# 2025_07_18_ftdi.net
KiCad netlist of a schematic drawn in EasyEDA Pro
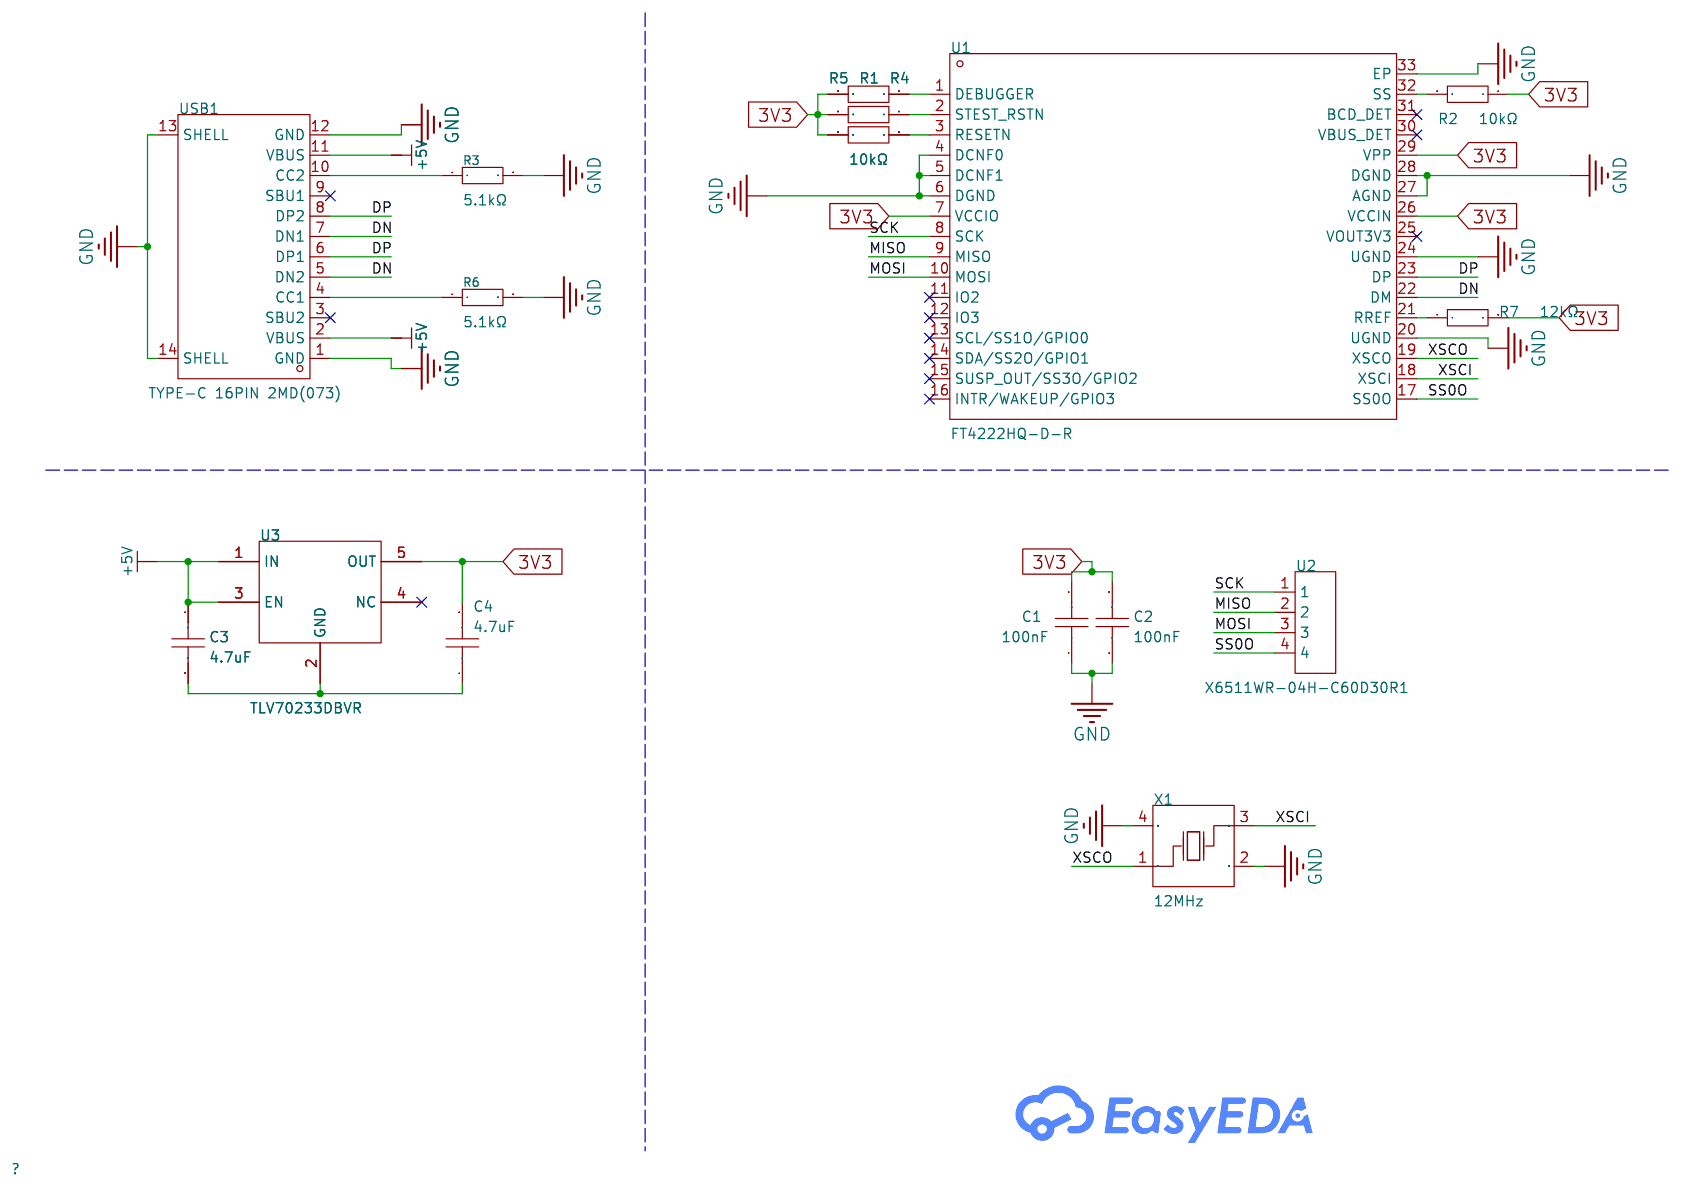
[diagram p0: schematic sheet]

(export (version "E")
  (design (tool "Eeschema 10.0.6"))
  (components
    (comp (ref "C1")
      (value "100nF")
      (footprint "easyedapro:C0402")
      (fields
        (field (name "Manufacturer Part") "CL05B104KO5NNNC")
        (field (name "Manufacturer") "SAMSUNG(三星)")
      )
      (libsource (lib "easyedapro") (part "CL05B104KO5NNNC"))
    )
    (comp (ref "C2")
      (value "100nF")
      (footprint "easyedapro:C0402")
      (fields
        (field (name "Manufacturer Part") "CL05B104KO5NNNC")
        (field (name "Manufacturer") "SAMSUNG(三星)")
      )
      (libsource (lib "easyedapro") (part "CL05B104KO5NNNC"))
    )
    (comp (ref "C3")
      (value "4.7uF")
      (footprint "easyedapro:C0402")
      (fields
        (field (name "Manufacturer Part") "CL05A475MQ5NRNC")
        (field (name "Manufacturer") "SAMSUNG(三星)")
      )
      (libsource (lib "easyedapro") (part "CL05A475MQ5NRNC_C307423"))
    )
    (comp (ref "C4")
      (value "4.7uF")
      (footprint "easyedapro:C0402")
      (fields
        (field (name "Manufacturer Part") "CL05A475MQ5NRNC")
        (field (name "Manufacturer") "SAMSUNG(三星)")
      )
      (libsource (lib "easyedapro") (part "CL05A475MQ5NRNC_C307423"))
    )
    (comp (ref "R1")
      (value "10kΩ")
      (footprint "easyedapro:R0603")
      (fields (field (name "Manufacturer Part") "RC0603FR-0710KL") (field (name "Manufacturer") "YAGEO(国巨)"))
      (libsource (lib "easyedapro") (part "RC0603FR-0710KL"))
    )
    (comp (ref "R2")
      (value "10kΩ")
      (footprint "easyedapro:R0603")
      (fields (field (name "Manufacturer Part") "RC0603FR-0710KL") (field (name "Manufacturer") "YAGEO(国巨)"))
      (libsource (lib "easyedapro") (part "RC0603FR-0710KL"))
    )
    (comp (ref "R3")
      (value "5.1kΩ")
      (footprint "easyedapro:R0402")
      (fields
        (field (name "Manufacturer Part") "0402WGF5101TCE")
        (field (name "Manufacturer") "UNI-ROYAL(厚声)")
      )
      (libsource (lib "easyedapro") (part "0402WGF5101TCE"))
    )
    (comp (ref "R4")
      (value "10kΩ")
      (footprint "easyedapro:R0603")
      (fields (field (name "Manufacturer Part") "RC0603FR-0710KL") (field (name "Manufacturer") "YAGEO(国巨)"))
      (libsource (lib "easyedapro") (part "RC0603FR-0710KL"))
    )
    (comp (ref "R5")
      (value "10kΩ")
      (footprint "easyedapro:R0603")
      (fields (field (name "Manufacturer Part") "RC0603FR-0710KL") (field (name "Manufacturer") "YAGEO(国巨)"))
      (libsource (lib "easyedapro") (part "RC0603FR-0710KL"))
    )
    (comp (ref "R6")
      (value "5.1kΩ")
      (footprint "easyedapro:R0402")
      (fields
        (field (name "Manufacturer Part") "0402WGF5101TCE")
        (field (name "Manufacturer") "UNI-ROYAL(厚声)")
      )
      (libsource (lib "easyedapro") (part "0402WGF5101TCE"))
    )
    (comp (ref "R7")
      (value "12kΩ")
      (footprint "easyedapro:R0402")
      (fields
        (field (name "Manufacturer Part") "0402WGF1202TCE")
        (field (name "Manufacturer") "UNI-ROYAL(厚声)")
      )
      (libsource (lib "easyedapro") (part "0402WGF1202TCE"))
    )
    (comp (ref "U1")
      (value "FT4222HQ-D-R")
      (footprint "easyedapro:QFN-32_L5.0-W5.0-P0.50-BL-EP3.7")
      (fields (field (name "Manufacturer") "FTDI(飞特帝亚)"))
      (libsource (lib "easyedapro") (part "FT4222HQ-D-R"))
    )
    (comp (ref "U2")
      (value "X6511WR-04H-C60D30R1")
      (footprint "easyedapro:HDR-TH_4P-P2.54-H-M-W7.7-P")
      (fields (field (name "Manufacturer") "XKB Connection(中国星坤)"))
      (libsource (lib "easyedapro") (part "X6511WR-04H-C30D60R1"))
    )
    (comp (ref "U3")
      (value "TLV70233DBVR")
      (footprint "easyedapro:SOT-23-5_L3.0-W1.7-P0.95-LS2.8-BR")
      (fields (field (name "Manufacturer") "TI(德州仪器)"))
      (libsource (lib "easyedapro") (part "TLV70233DBVR"))
    )
    (comp (ref "USB1")
      (value "TYPE-C 16PIN 2MD(073)")
      (footprint "easyedapro:USB-C-SMD_TYPE-C-6PIN-2MD-073")
      (fields (field (name "Manufacturer") "SHOU HAN(首韩)"))
      (libsource (lib "easyedapro") (part "TYPE-C 16PIN 2MD(073)"))
    )
    (comp (ref "X1")
      (value "12MHz")
      (footprint "easyedapro:CRYSTAL-SMD_4P-L3.2-W2.5-BL")
      (fields (field (name "Manufacturer Part") "X322512MSB4SI") (field (name "Manufacturer") "YXC(扬兴晶振)"))
      (libsource (lib "easyedapro") (part "X322512MSB4SI"))
    )
  )
  (nets
    (net (code "1") (name "+5V") (class "Default")
      (node (ref "C3") (pin "1") (pinfunction "1_1") (pintype "unspecified"))
      (node (ref "U3") (pin "1") (pinfunction "IN_1") (pintype "unspecified"))
      (node (ref "U3") (pin "3") (pinfunction "EN_3") (pintype "unspecified"))
      (node (ref "USB1") (pin "11") (pinfunction "VBUS_11") (pintype "unspecified"))
      (node (ref "USB1") (pin "2") (pinfunction "VBUS_2") (pintype "unspecified"))
    )
    (net (code "2") (name "/DN") (class "Default")
      (node (ref "U1") (pin "22") (pinfunction "DM_22") (pintype "unspecified"))
      (node (ref "USB1") (pin "5") (pinfunction "DN2_5") (pintype "unspecified"))
      (node (ref "USB1") (pin "7") (pinfunction "DN1_7") (pintype "unspecified"))
    )
    (net (code "3") (name "/DP") (class "Default")
      (node (ref "U1") (pin "23") (pinfunction "DP_23") (pintype "unspecified"))
      (node (ref "USB1") (pin "6") (pinfunction "DP1_6") (pintype "unspecified"))
      (node (ref "USB1") (pin "8") (pinfunction "DP2_8") (pintype "unspecified"))
    )
    (net (code "4") (name "/MISO") (class "Default")
      (node (ref "U1") (pin "9") (pinfunction "MISO_9") (pintype "unspecified"))
      (node (ref "U2") (pin "2") (pinfunction "2_2") (pintype "unspecified"))
    )
    (net (code "5") (name "/MOSI") (class "Default")
      (node (ref "U1") (pin "10") (pinfunction "MOSI_10") (pintype "unspecified"))
      (node (ref "U2") (pin "3") (pinfunction "3_3") (pintype "unspecified"))
    )
    (net (code "6") (name "/SCK") (class "Default")
      (node (ref "U1") (pin "8") (pinfunction "SCK_8") (pintype "unspecified"))
      (node (ref "U2") (pin "1") (pinfunction "1_1") (pintype "unspecified"))
    )
    (net (code "7") (name "/SS0O") (class "Default")
      (node (ref "U1") (pin "17") (pinfunction "SS0O_17") (pintype "unspecified"))
      (node (ref "U2") (pin "4") (pinfunction "4_4") (pintype "unspecified"))
    )
    (net (code "8") (name "/XSCI") (class "Default")
      (node (ref "U1") (pin "18") (pinfunction "XSCI_18") (pintype "unspecified"))
      (node (ref "X1") (pin "3") (pinfunction "OSC2_3") (pintype "unspecified"))
    )
    (net (code "9") (name "/XSCO") (class "Default")
      (node (ref "U1") (pin "19") (pinfunction "XSCO_19") (pintype "unspecified"))
      (node (ref "X1") (pin "1") (pinfunction "OSC1_1") (pintype "unspecified"))
    )
    (net (code "10") (name "3V3") (class "Default")
      (node (ref "C1") (pin "2") (pinfunction "2_2") (pintype "unspecified"))
      (node (ref "C2") (pin "2") (pinfunction "2_2") (pintype "unspecified"))
      (node (ref "C4") (pin "2") (pinfunction "2_2") (pintype "unspecified"))
      (node (ref "R1") (pin "2") (pinfunction "2_2") (pintype "input"))
      (node (ref "R2") (pin "1") (pinfunction "1_1") (pintype "input"))
      (node (ref "R4") (pin "2") (pinfunction "2_2") (pintype "input"))
      (node (ref "R5") (pin "2") (pinfunction "2_2") (pintype "input"))
      (node (ref "R7") (pin "2") (pinfunction "2_2") (pintype "input"))
      (node (ref "U1") (pin "26") (pinfunction "VCCIN_26") (pintype "unspecified"))
      (node (ref "U1") (pin "29") (pinfunction "VPP_29") (pintype "unspecified"))
      (node (ref "U1") (pin "7") (pinfunction "VCCIO_7") (pintype "unspecified"))
      (node (ref "U3") (pin "5") (pinfunction "OUT_5") (pintype "unspecified"))
    )
    (net (code "11") (name "GND") (class "Default")
      (node (ref "C1") (pin "1") (pinfunction "1_1") (pintype "unspecified"))
      (node (ref "C2") (pin "1") (pinfunction "1_1") (pintype "unspecified"))
      (node (ref "R3") (pin "2") (pinfunction "2_2") (pintype "input"))
      (node (ref "R6") (pin "2") (pinfunction "2_2") (pintype "input"))
      (node (ref "U1") (pin "20") (pinfunction "UGND_20") (pintype "unspecified"))
      (node (ref "U1") (pin "24") (pinfunction "UGND_24") (pintype "unspecified"))
      (node (ref "U1") (pin "27") (pinfunction "AGND_27") (pintype "unspecified"))
      (node (ref "U1") (pin "28") (pinfunction "DGND_28") (pintype "unspecified"))
      (node (ref "U1") (pin "33") (pinfunction "EP_33") (pintype "unspecified"))
      (node (ref "U1") (pin "4") (pinfunction "DCNF0_4") (pintype "unspecified"))
      (node (ref "U1") (pin "5") (pinfunction "DCNF1_5") (pintype "unspecified"))
      (node (ref "U1") (pin "6") (pinfunction "DGND_6") (pintype "unspecified"))
      (node (ref "USB1") (pin "1") (pinfunction "GND_1") (pintype "unspecified"))
      (node (ref "USB1") (pin "12") (pinfunction "GND_12") (pintype "unspecified"))
      (node (ref "USB1") (pin "13") (pinfunction "SHELL_13") (pintype "unspecified"))
      (node (ref "USB1") (pin "14") (pinfunction "SHELL_14") (pintype "unspecified"))
      (node (ref "X1") (pin "2") (pinfunction "GND_2") (pintype "unspecified"))
      (node (ref "X1") (pin "4") (pinfunction "GND_4") (pintype "unspecified"))
    )
    (net (code "12") (name "Net-(U1-DEBUGGER)") (class "Default")
      (node (ref "R1") (pin "1") (pinfunction "1_1") (pintype "input"))
      (node (ref "U1") (pin "1") (pinfunction "DEBUGGER_1") (pintype "unspecified"))
    )
    (net (code "13") (name "Net-(U1-RESETN)") (class "Default")
      (node (ref "R5") (pin "1") (pinfunction "1_1") (pintype "input"))
      (node (ref "U1") (pin "3") (pinfunction "RESETN_3") (pintype "unspecified"))
    )
    (net (code "14") (name "Net-(U1-RREF)") (class "Default")
      (node (ref "R7") (pin "1") (pinfunction "1_1") (pintype "input"))
      (node (ref "U1") (pin "21") (pinfunction "RREF_21") (pintype "unspecified"))
    )
    (net (code "15") (name "Net-(U1-SS)") (class "Default")
      (node (ref "R2") (pin "2") (pinfunction "2_2") (pintype "input"))
      (node (ref "U1") (pin "32") (pinfunction "SS_32") (pintype "unspecified"))
    )
    (net (code "16") (name "Net-(U1-STEST_RSTN)") (class "Default")
      (node (ref "R4") (pin "1") (pinfunction "1_1") (pintype "input"))
      (node (ref "U1") (pin "2") (pinfunction "STEST_RSTN_2") (pintype "unspecified"))
    )
    (net (code "17") (name "Net-(U3-GND)") (class "Default")
      (node (ref "C3") (pin "2") (pinfunction "2_2") (pintype "unspecified"))
      (node (ref "C4") (pin "1") (pinfunction "1_1") (pintype "unspecified"))
      (node (ref "U3") (pin "2") (pinfunction "GND_2") (pintype "unspecified"))
    )
    (net (code "18") (name "Net-(USB1-CC1)") (class "Default")
      (node (ref "R6") (pin "1") (pinfunction "1_1") (pintype "input"))
      (node (ref "USB1") (pin "4") (pinfunction "CC1_4") (pintype "unspecified"))
    )
    (net (code "19") (name "Net-(USB1-CC2)") (class "Default")
      (node (ref "R3") (pin "1") (pinfunction "1_1") (pintype "input"))
      (node (ref "USB1") (pin "10") (pinfunction "CC2_10") (pintype "unspecified"))
    )
    (net (code "20") (name "unconnected-(U1-BCD_DET-Pad31)") (class "Default")
      (node (ref "U1") (pin "31") (pinfunction "BCD_DET_31") (pintype "unspecified+no_connect"))
    )
    (net (code "21") (name "unconnected-(U1-INTR{slash}WAKEUP{slash}GPIO3-Pad16)") (class "Default")
      (node (ref "U1") (pin "16") (pinfunction "INTR/WAKEUP/GPIO3_16") (pintype "unspecified+no_connect"))
    )
    (net (code "22") (name "unconnected-(U1-IO2-Pad11)") (class "Default")
      (node (ref "U1") (pin "11") (pinfunction "IO2_11") (pintype "unspecified+no_connect"))
    )
    (net (code "23") (name "unconnected-(U1-IO3-Pad12)") (class "Default")
      (node (ref "U1") (pin "12") (pinfunction "IO3_12") (pintype "unspecified+no_connect"))
    )
    (net (code "24") (name "unconnected-(U1-SCL{slash}SS1O{slash}GPIO0-Pad13)") (class "Default")
      (node (ref "U1") (pin "13") (pinfunction "SCL/SS1O/GPIO0_13") (pintype "unspecified+no_connect"))
    )
    (net (code "25") (name "unconnected-(U1-SDA{slash}SS2O{slash}GPIO1-Pad14)") (class "Default")
      (node (ref "U1") (pin "14") (pinfunction "SDA/SS2O/GPIO1_14") (pintype "unspecified+no_connect"))
    )
    (net (code "26") (name "unconnected-(U1-SUSP_OUT{slash}SS3O{slash}GPIO2-Pad15)") (class "Default")
      (node (ref "U1") (pin "15") (pinfunction "SUSP_OUT/SS3O/GPIO2_15") (pintype "unspecified+no_connect"))
    )
    (net (code "27") (name "unconnected-(U1-VBUS_DET-Pad30)") (class "Default")
      (node (ref "U1") (pin "30") (pinfunction "VBUS_DET_30") (pintype "unspecified+no_connect"))
    )
    (net (code "28") (name "unconnected-(U1-VOUT3V3-Pad25)") (class "Default")
      (node (ref "U1") (pin "25") (pinfunction "VOUT3V3_25") (pintype "unspecified+no_connect"))
    )
    (net (code "29") (name "unconnected-(U3-NC-Pad4)") (class "Default")
      (node (ref "U3") (pin "4") (pinfunction "NC_4") (pintype "unspecified+no_connect"))
    )
    (net (code "30") (name "unconnected-(USB1-SBU1-Pad9)") (class "Default")
      (node (ref "USB1") (pin "9") (pinfunction "SBU1_9") (pintype "unspecified+no_connect"))
    )
    (net (code "31") (name "unconnected-(USB1-SBU2-Pad3)") (class "Default")
      (node (ref "USB1") (pin "3") (pinfunction "SBU2_3") (pintype "unspecified+no_connect"))
    )
  )
)
